# MCU.net
KiCad netlist of a schematic drawn in Altium Designer
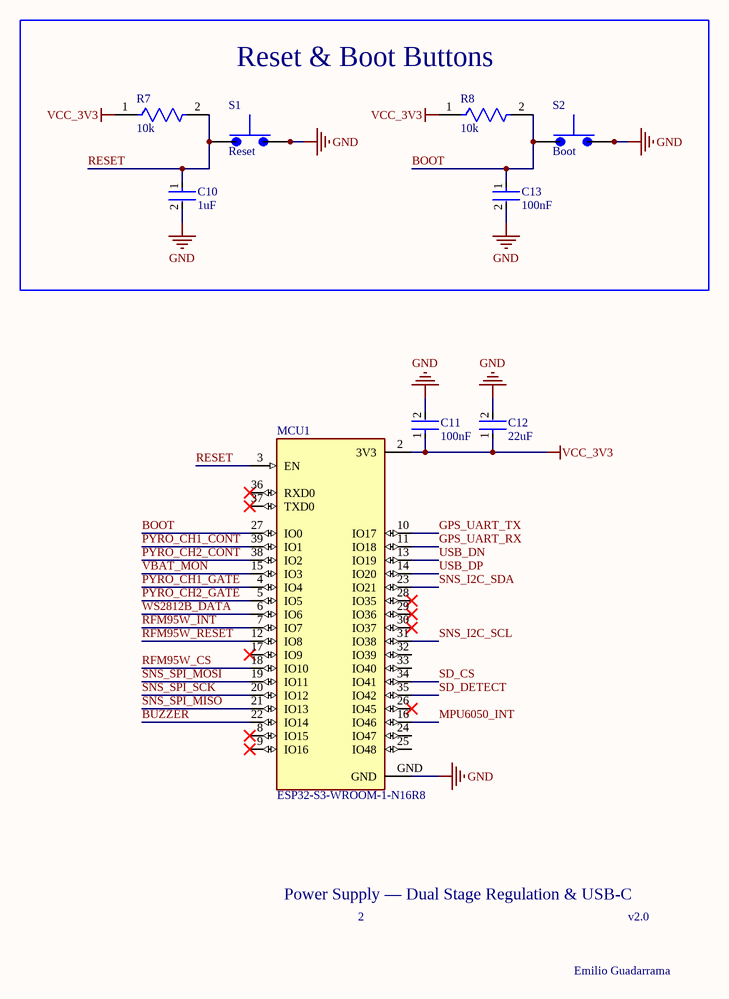
[diagram p0: MCU.SchDoc]

(export (version "E")
  (design (tool "Eeschema 10.0.6"))
  (components
    (comp (ref "C10")
      (value "1uF")
      (footprint "FP-C0805C-DN-MFG")
      (description "CAP CER 0.1UF 50V X7R 0805")
      (fields
        (field (name "MANUFACTURER PART NUMBER") "C0805C104K5RACTU")
        (field (name "MANUFACTURER") "KEMET")
      )
      (libsource (lib "Altium Content Vault") (part "b4654b650e69147ec39a6b967a45e02"))
    )
    (comp (ref "C11")
      (value "100nF")
      (footprint "FP-C0805C-DN-MFG")
      (description "CAP CER 0.1UF 50V X7R 0805")
      (fields
        (field (name "MANUFACTURER PART NUMBER") "C0805C104K5RACTU")
        (field (name "MANUFACTURER") "KEMET")
      )
      (libsource (lib "Altium Content Vault") (part "b4654b650e69147ec39a6b967a45e02"))
    )
    (comp (ref "C12")
      (value "22uF")
      (footprint "FP-C0805C-DN-MFG")
      (description "CAP CER 0.1UF 50V X7R 0805")
      (fields
        (field (name "MANUFACTURER PART NUMBER") "C0805C104K5RACTU")
        (field (name "MANUFACTURER") "KEMET")
      )
      (libsource (lib "Altium Content Vault") (part "b4654b650e69147ec39a6b967a45e02"))
    )
    (comp (ref "C13")
      (value "100nF")
      (footprint "FP-C0805C-DN-MFG")
      (description "CAP CER 0.1UF 50V X7R 0805")
      (fields
        (field (name "MANUFACTURER PART NUMBER") "C0805C104K5RACTU")
        (field (name "MANUFACTURER") "KEMET")
      )
      (libsource (lib "Altium Content Vault") (part "b4654b650e69147ec39a6b967a45e02"))
    )
    (comp (ref "MCU1")
      (value "ESP32-S3-WROOM-1-N16R8")
      (footprint "XCVR_ESP32-S3-WROOM-1-N16R2")
      (description "Bluetooth, WiFi 802.11b/g/n, Bluetooth v5.0 Transceiver Module 2.4GHz PCB Trace Surface Mount")
      (fields (field (name "MF") "Espressif Systems") (field (name "MP") "ESP32S3WROOM1N16R2"))
      (libsource (lib "ESP32-S3-WROOM-1-N16R2") (part "ESP32-S3-WROOM-1-N16R2"))
    )
    (comp (ref "R7")
      (value "10k")
      (footprint "FP-MCT0603-IPC_A")
      (description "RES SMD 100 OHM 1% 1/8W 0603")
      (fields (field (name "TOLERANCE") "0.1%"))
      (libsource (lib "Altium Content Vault") (part "1029c3af85768c4190bb7ad29bc67b5"))
    )
    (comp (ref "R8")
      (value "10k")
      (footprint "FP-MCT0603-IPC_A")
      (description "RES SMD 100 OHM 1% 1/8W 0603")
      (fields (field (name "TOLERANCE") "0.1%"))
      (libsource (lib "Altium Content Vault") (part "1029c3af85768c4190bb7ad29bc67b5"))
    )
    (comp (ref "S1")
      (value "Reset")
      (footprint "SW_SKRPABE010")
      (description "Switch Tactile N.O. SPST Button J-Bend 0.05A 16VDC 1.57N SMD Automotive T/R")
      (fields (field (name "MF") "ALPS") (field (name "MP") "SKRPABE010"))
      (libsource (lib "Button-SKRPABE010") (part "SKRPABE010"))
    )
    (comp (ref "S2")
      (value "Boot")
      (footprint "SW_SKRPABE010")
      (description "Switch Tactile N.O. SPST Button J-Bend 0.05A 16VDC 1.57N SMD Automotive T/R")
      (fields (field (name "MF") "ALPS") (field (name "MP") "SKRPABE010"))
      (libsource (lib "Button-SKRPABE010") (part "SKRPABE010"))
    )
  )
  (nets
    (net (code "1") (name "/BOOT") (class "Default")
      (node (ref "C13") (pin "1") (pinfunction "1_1") (pintype "passive"))
      (node (ref "MCU1") (pin "27") (pinfunction "IO0_27") (pintype "bidirectional"))
      (node (ref "R8") (pin "2") (pinfunction "2_2") (pintype "passive"))
      (node (ref "S2") (pin "1") (pinfunction "1_1") (pintype "passive"))
      (node (ref "S2") (pin "2") (pinfunction "1_2") (pintype "passive"))
    )
    (net (code "2") (name "/BUZZER") (class "Default")
      (node (ref "MCU1") (pin "22") (pinfunction "IO14_22") (pintype "bidirectional"))
    )
    (net (code "3") (name "/GPS_UART_RX") (class "Default")
      (node (ref "MCU1") (pin "11") (pinfunction "IO18_11") (pintype "bidirectional"))
    )
    (net (code "4") (name "/GPS_UART_TX") (class "Default")
      (node (ref "MCU1") (pin "10") (pinfunction "IO17_10") (pintype "bidirectional"))
    )
    (net (code "5") (name "/MPU6050_INT") (class "Default")
      (node (ref "MCU1") (pin "16") (pinfunction "IO46_16") (pintype "bidirectional"))
    )
    (net (code "6") (name "/PYRO_CH1_CONT") (class "Default")
      (node (ref "MCU1") (pin "39") (pinfunction "IO1_39") (pintype "bidirectional"))
    )
    (net (code "7") (name "/PYRO_CH1_GATE") (class "Default")
      (node (ref "MCU1") (pin "4") (pinfunction "IO4_4") (pintype "bidirectional"))
    )
    (net (code "8") (name "/PYRO_CH2_CONT") (class "Default")
      (node (ref "MCU1") (pin "38") (pinfunction "IO2_38") (pintype "bidirectional"))
    )
    (net (code "9") (name "/PYRO_CH2_GATE") (class "Default")
      (node (ref "MCU1") (pin "5") (pinfunction "IO5_5") (pintype "bidirectional"))
    )
    (net (code "10") (name "/RESET") (class "Default")
      (node (ref "C10") (pin "1") (pinfunction "1_1") (pintype "passive"))
      (node (ref "MCU1") (pin "3") (pinfunction "EN_3") (pintype "input"))
      (node (ref "R7") (pin "2") (pinfunction "2_2") (pintype "passive"))
      (node (ref "S1") (pin "1") (pinfunction "1_1") (pintype "passive"))
      (node (ref "S1") (pin "2") (pinfunction "1_2") (pintype "passive"))
    )
    (net (code "11") (name "/RFM95W_CS") (class "Default")
      (node (ref "MCU1") (pin "18") (pinfunction "IO10_18") (pintype "bidirectional"))
    )
    (net (code "12") (name "/RFM95W_INT") (class "Default")
      (node (ref "MCU1") (pin "7") (pinfunction "IO7_7") (pintype "bidirectional"))
    )
    (net (code "13") (name "/RFM95W_RESET") (class "Default")
      (node (ref "MCU1") (pin "12") (pinfunction "IO8_12") (pintype "bidirectional"))
    )
    (net (code "14") (name "/SD_CS") (class "Default")
      (node (ref "MCU1") (pin "34") (pinfunction "IO41_34") (pintype "bidirectional"))
    )
    (net (code "15") (name "/SD_DETECT") (class "Default")
      (node (ref "MCU1") (pin "35") (pinfunction "IO42_35") (pintype "bidirectional"))
    )
    (net (code "16") (name "/SNS_I2C_SCL") (class "Default")
      (node (ref "MCU1") (pin "31") (pinfunction "IO38_31") (pintype "bidirectional"))
    )
    (net (code "17") (name "/SNS_I2C_SDA") (class "Default")
      (node (ref "MCU1") (pin "23") (pinfunction "IO21_23") (pintype "bidirectional"))
    )
    (net (code "18") (name "/SNS_SPI_MISO") (class "Default")
      (node (ref "MCU1") (pin "21") (pinfunction "IO13_21") (pintype "bidirectional"))
    )
    (net (code "19") (name "/SNS_SPI_MOSI") (class "Default")
      (node (ref "MCU1") (pin "19") (pinfunction "IO11_19") (pintype "bidirectional"))
    )
    (net (code "20") (name "/SNS_SPI_SCK") (class "Default")
      (node (ref "MCU1") (pin "20") (pinfunction "IO12_20") (pintype "bidirectional"))
    )
    (net (code "21") (name "/USB_DN") (class "Default")
      (node (ref "MCU1") (pin "13") (pinfunction "IO19_13") (pintype "bidirectional"))
    )
    (net (code "22") (name "/USB_DP") (class "Default")
      (node (ref "MCU1") (pin "14") (pinfunction "IO20_14") (pintype "bidirectional"))
    )
    (net (code "23") (name "/VBAT_MON") (class "Default")
      (node (ref "MCU1") (pin "15") (pinfunction "IO3_15") (pintype "bidirectional"))
    )
    (net (code "24") (name "/WS2812B_DATA") (class "Default")
      (node (ref "MCU1") (pin "6") (pinfunction "IO6_6") (pintype "bidirectional"))
    )
    (net (code "25") (name "GND") (class "Default")
      (node (ref "C10") (pin "2") (pinfunction "2_2") (pintype "passive"))
      (node (ref "C11") (pin "2") (pinfunction "2_2") (pintype "passive"))
      (node (ref "C12") (pin "2") (pinfunction "2_2") (pintype "passive"))
      (node (ref "C13") (pin "2") (pinfunction "2_2") (pintype "passive"))
      (node (ref "MCU1") (pin "GND") (pinfunction "GND_GND") (pintype "power_in"))
      (node (ref "S1") (pin "3") (pinfunction "2_3") (pintype "passive"))
      (node (ref "S1") (pin "4") (pinfunction "2_4") (pintype "passive"))
      (node (ref "S2") (pin "3") (pinfunction "2_3") (pintype "passive"))
      (node (ref "S2") (pin "4") (pinfunction "2_4") (pintype "passive"))
    )
    (net (code "26") (name "VCC_3V3") (class "Default")
      (node (ref "C11") (pin "1") (pinfunction "1_1") (pintype "passive"))
      (node (ref "C12") (pin "1") (pinfunction "1_1") (pintype "passive"))
      (node (ref "MCU1") (pin "2") (pinfunction "3V3_2") (pintype "power_in"))
      (node (ref "R7") (pin "1") (pinfunction "1_1") (pintype "passive"))
      (node (ref "R8") (pin "1") (pinfunction "1_1") (pintype "passive"))
    )
    (net (code "27") (name "unconnected-(MCU1-IO9-Pad17)") (class "Default")
      (node (ref "MCU1") (pin "17") (pinfunction "IO9_17") (pintype "bidirectional+no_connect"))
    )
    (net (code "28") (name "unconnected-(MCU1-IO15-Pad8)") (class "Default")
      (node (ref "MCU1") (pin "8") (pinfunction "IO15_8") (pintype "bidirectional+no_connect"))
    )
    (net (code "29") (name "unconnected-(MCU1-IO16-Pad9)") (class "Default")
      (node (ref "MCU1") (pin "9") (pinfunction "IO16_9") (pintype "bidirectional+no_connect"))
    )
    (net (code "30") (name "unconnected-(MCU1-IO35-Pad28)") (class "Default")
      (node (ref "MCU1") (pin "28") (pinfunction "IO35_28") (pintype "bidirectional+no_connect"))
    )
    (net (code "31") (name "unconnected-(MCU1-IO36-Pad29)") (class "Default")
      (node (ref "MCU1") (pin "29") (pinfunction "IO36_29") (pintype "bidirectional+no_connect"))
    )
    (net (code "32") (name "unconnected-(MCU1-IO37-Pad30)") (class "Default")
      (node (ref "MCU1") (pin "30") (pinfunction "IO37_30") (pintype "bidirectional+no_connect"))
    )
    (net (code "33") (name "unconnected-(MCU1-IO39-Pad32)") (class "Default")
      (node (ref "MCU1") (pin "32") (pinfunction "IO39_32") (pintype "bidirectional"))
    )
    (net (code "34") (name "unconnected-(MCU1-IO40-Pad33)") (class "Default")
      (node (ref "MCU1") (pin "33") (pinfunction "IO40_33") (pintype "bidirectional"))
    )
    (net (code "35") (name "unconnected-(MCU1-IO45-Pad26)") (class "Default")
      (node (ref "MCU1") (pin "26") (pinfunction "IO45_26") (pintype "bidirectional+no_connect"))
    )
    (net (code "36") (name "unconnected-(MCU1-IO47-Pad24)") (class "Default")
      (node (ref "MCU1") (pin "24") (pinfunction "IO47_24") (pintype "bidirectional"))
    )
    (net (code "37") (name "unconnected-(MCU1-IO48-Pad25)") (class "Default")
      (node (ref "MCU1") (pin "25") (pinfunction "IO48_25") (pintype "bidirectional"))
    )
    (net (code "38") (name "unconnected-(MCU1-RXD0-Pad36)") (class "Default")
      (node (ref "MCU1") (pin "36") (pinfunction "RXD0_36") (pintype "bidirectional+no_connect"))
    )
    (net (code "39") (name "unconnected-(MCU1-TXD0-Pad37)") (class "Default")
      (node (ref "MCU1") (pin "37") (pinfunction "TXD0_37") (pintype "bidirectional+no_connect"))
    )
  )
)
